# portal.net
KiCad netlist of a schematic drawn in EAGLE
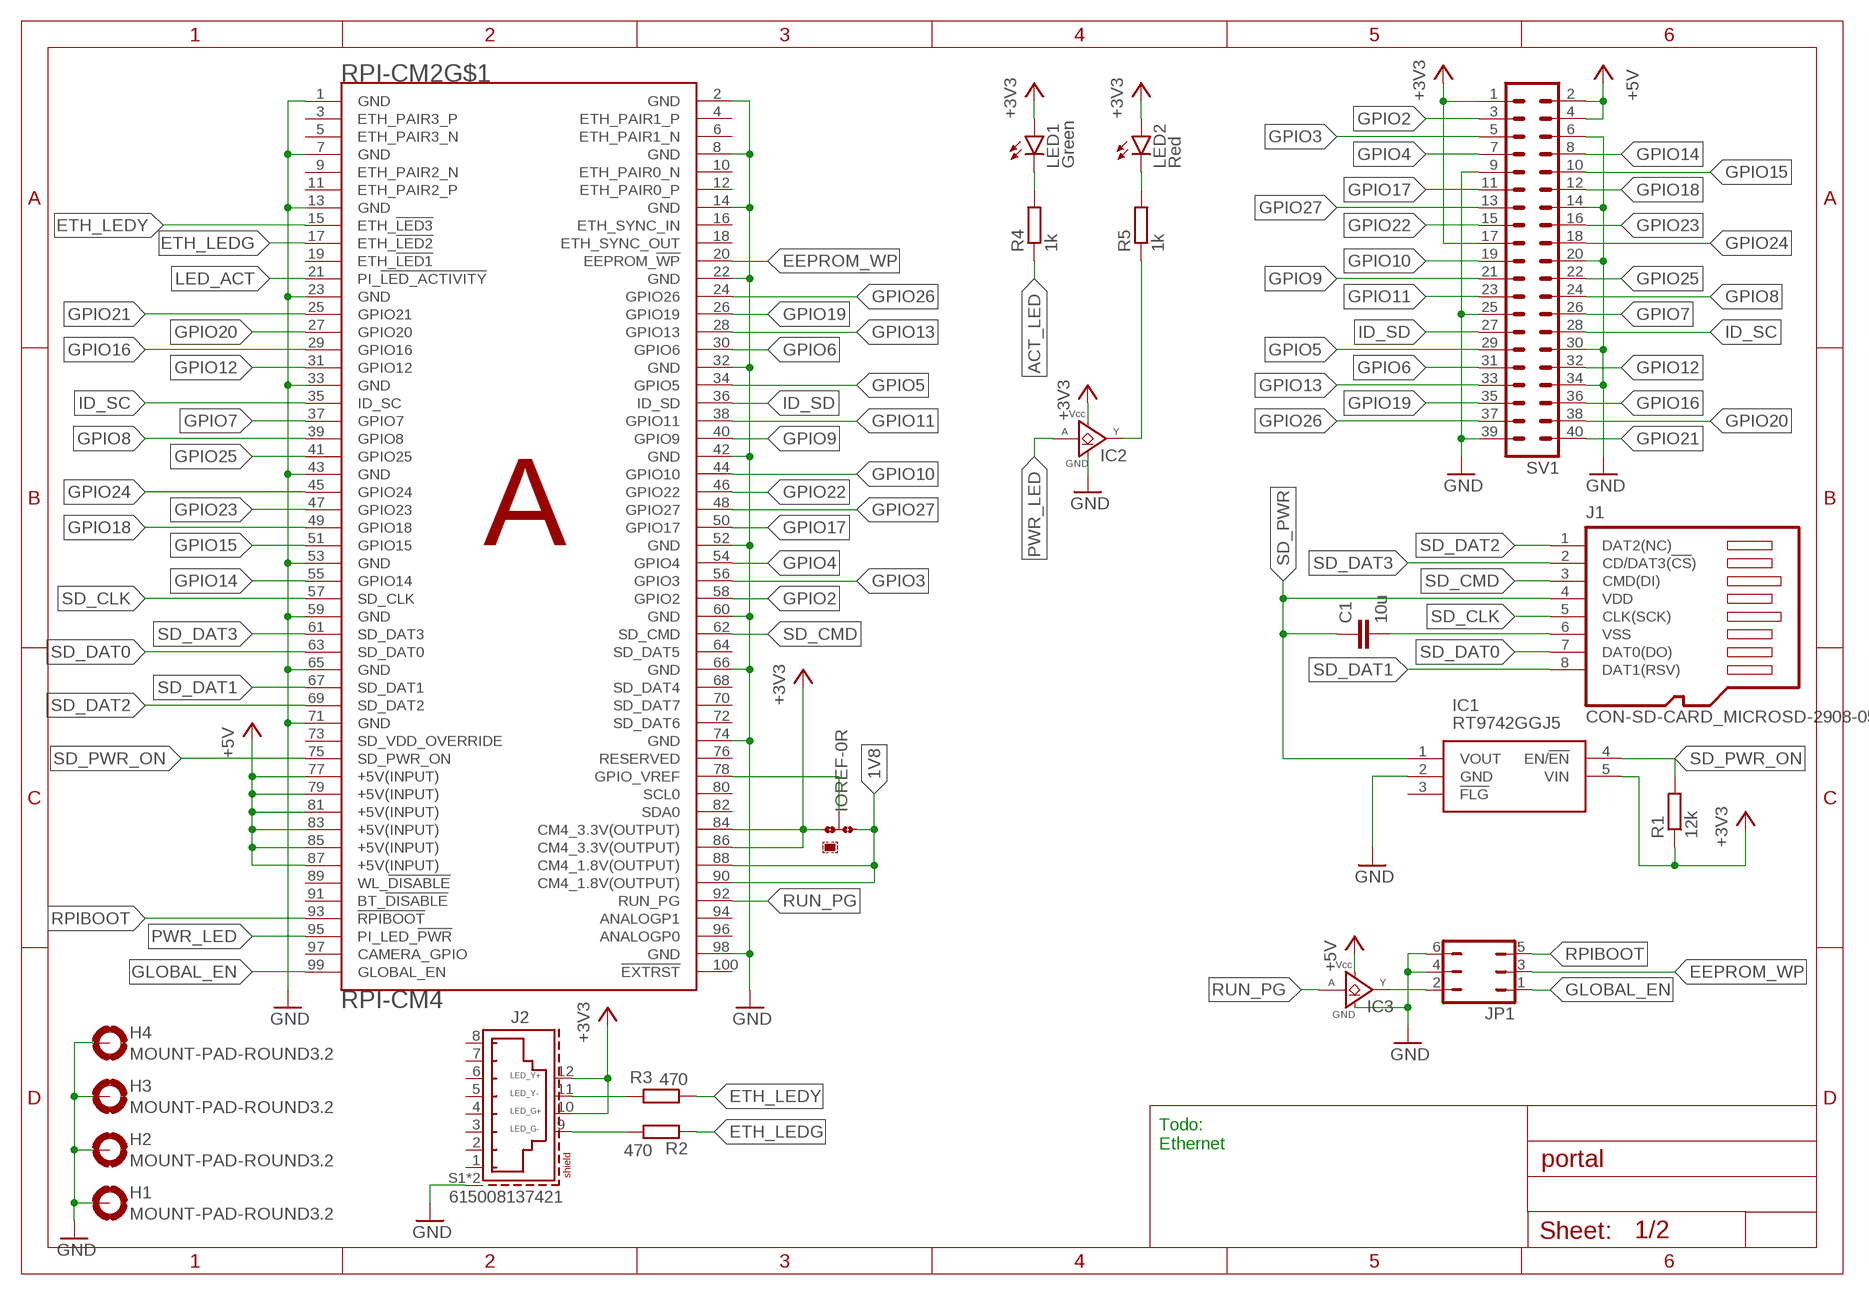
[diagram p0: schematic, sheet 1]
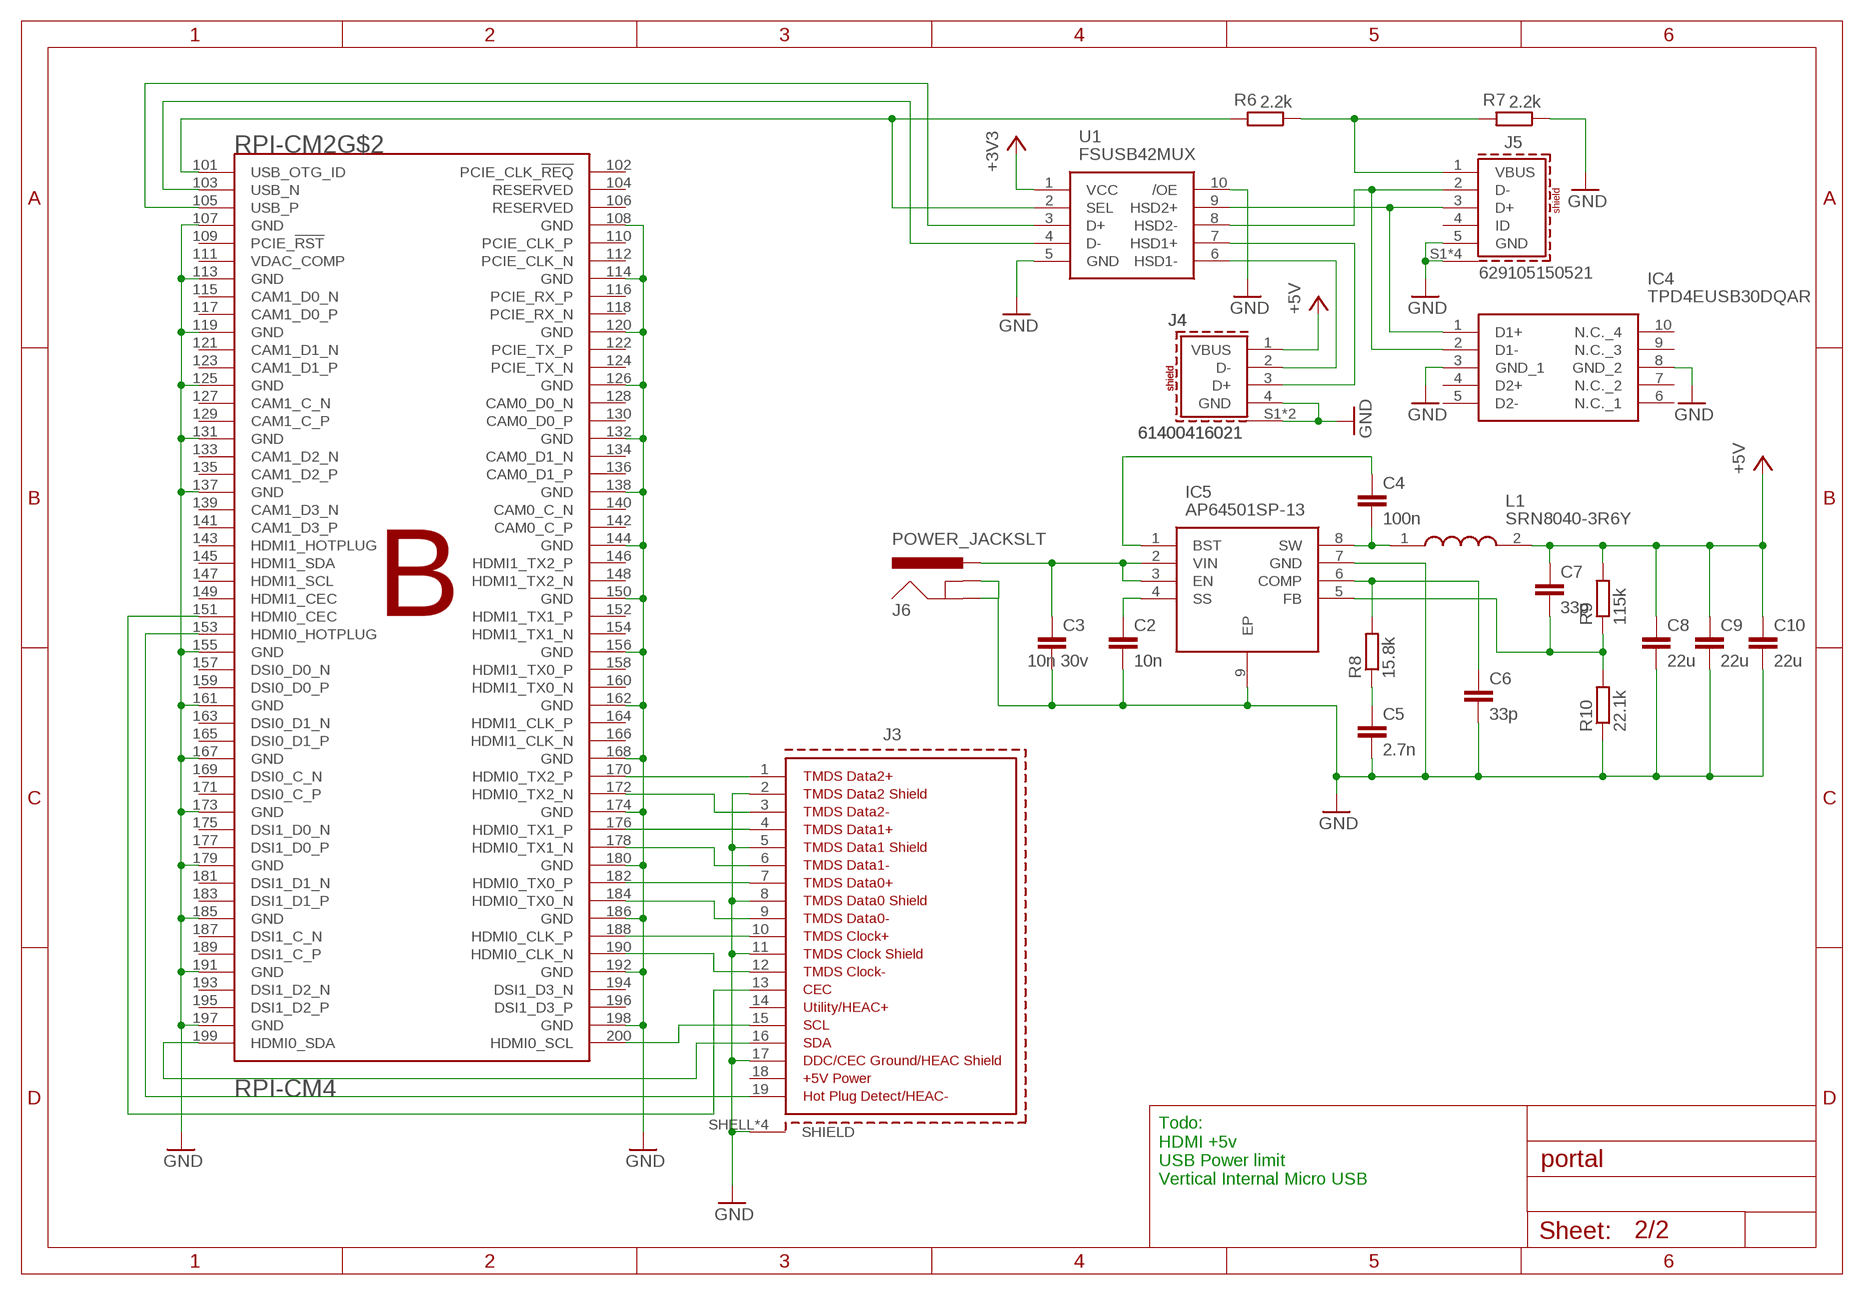
[diagram p1: schematic, sheet 2]

(export (version "E")
  (design (tool "Eeschema 10.0.6"))
  (components
    (comp (ref "C1")
      (value "10u")
      (footprint "eagle-import:C0805")
      (libsource (lib "eagle-import") (part "C-EUC0805"))
    )
    (comp (ref "H1")
      (value "MOUNT-PAD-ROUND3.2")
      (footprint "eagle-import:3,2-PAD")
      (libsource (lib "eagle-import") (part "MOUNT-PAD-ROUND3.2"))
    )
    (comp (ref "H2")
      (value "MOUNT-PAD-ROUND3.2")
      (footprint "eagle-import:3,2-PAD")
      (libsource (lib "eagle-import") (part "MOUNT-PAD-ROUND3.2"))
    )
    (comp (ref "H3")
      (value "MOUNT-PAD-ROUND3.2")
      (footprint "eagle-import:3,2-PAD")
      (libsource (lib "eagle-import") (part "MOUNT-PAD-ROUND3.2"))
    )
    (comp (ref "H4")
      (value "MOUNT-PAD-ROUND3.2")
      (footprint "eagle-import:3,2-PAD")
      (libsource (lib "eagle-import") (part "MOUNT-PAD-ROUND3.2"))
    )
    (comp (ref "IC1")
      (value "RT9742GGJ5")
      (footprint "eagle-import:SOT94P280X100-5N")
      (libsource (lib "eagle-import") (part "RT9742GGJ5"))
    )
    (comp (ref "IC2")
      (value "GHI-IC_SN74LVC1G07DCK")
      (footprint "eagle-import:GHI-IC_SC70(TI-DCK)")
      (libsource (lib "eagle-import") (part "GHI-IC_SN74LVC1G07DCK"))
    )
    (comp (ref "IC3")
      (value "GHI-IC_SN74LVC1G07DCK")
      (footprint "eagle-import:GHI-IC_SC70(TI-DCK)")
      (libsource (lib "eagle-import") (part "GHI-IC_SN74LVC1G07DCK"))
    )
    (comp (ref "IOREF")
      (value "0R-JUMPA")
      (footprint "eagle-import:A0R-JMP")
      (libsource (lib "eagle-import") (part "0R-JUMPA"))
    )
    (comp (ref "J1")
      (value "CON-SD-CARD_MICROSD-2908-05")
      (footprint "eagle-import:CON-SD-CARD_2908-05")
      (libsource (lib "eagle-import") (part "CON-SD-CARD_MICROSD-2908-05"))
    )
    (comp (ref "J2")
      (value "615008137421")
      (footprint "eagle-import:615008137421")
      (libsource (lib "eagle-import") (part "615008137421"))
    )
    (comp (ref "JP1")
      (value "JP3Q")
      (footprint "eagle-import:JP3Q")
      (libsource (lib "eagle-import") (part "JP3Q"))
    )
    (comp (ref "LED1")
      (value "Green")
      (footprint "eagle-import:CHIP-LED0805")
      (libsource (lib "eagle-import") (part "LEDCHIP-LED0805"))
    )
    (comp (ref "LED2")
      (value "Red")
      (footprint "eagle-import:CHIP-LED0805")
      (libsource (lib "eagle-import") (part "LEDCHIP-LED0805"))
    )
    (comp (ref "R1")
      (value "12k")
      (footprint "eagle-import:R0805")
      (libsource (lib "eagle-import") (part "resistor_348_R-EU_R0805"))
    )
    (comp (ref "R2")
      (value "470")
      (footprint "eagle-import:R0805")
      (libsource (lib "eagle-import") (part "R-EU_R0805"))
    )
    (comp (ref "R3")
      (value "470")
      (footprint "eagle-import:R0805")
      (libsource (lib "eagle-import") (part "R-EU_R0805"))
    )
    (comp (ref "R4")
      (value "1k")
      (footprint "eagle-import:R0805")
      (libsource (lib "eagle-import") (part "R-EU_R0805"))
    )
    (comp (ref "R5")
      (value "1k")
      (footprint "eagle-import:R0805")
      (libsource (lib "eagle-import") (part "R-EU_R0805"))
    )
    (comp (ref "RPI-CM2")
      (value "RPI-CM4")
      (footprint "eagle-import:RPI-CM4")
      (libsource (lib "eagle-import") (part "RPI-CM4"))
    )
    (comp (ref "SV1")
      (value "MA20-2")
      (footprint "eagle-import:MA20-2")
      (libsource (lib "eagle-import") (part "MA20-2"))
    )
    (comp (ref "C2")
      (value "10n")
      (footprint "eagle-import:C0805")
      (libsource (lib "eagle-import") (part "C-EUC0805"))
    )
    (comp (ref "C3")
      (value "10n 30v")
      (footprint "eagle-import:C0805")
      (libsource (lib "eagle-import") (part "C-EUC0805"))
    )
    (comp (ref "C4")
      (value "100n")
      (footprint "eagle-import:C0805")
      (libsource (lib "eagle-import") (part "C-EUC0805"))
    )
    (comp (ref "C5")
      (value "2.7n")
      (footprint "eagle-import:C0805")
      (libsource (lib "eagle-import") (part "C-EUC0805"))
    )
    (comp (ref "C6")
      (value "33p")
      (footprint "eagle-import:C0805")
      (libsource (lib "eagle-import") (part "C-EUC0805"))
    )
    (comp (ref "C7")
      (value "33p")
      (footprint "eagle-import:C0805")
      (libsource (lib "eagle-import") (part "C-EUC0805"))
    )
    (comp (ref "C8")
      (value "22u")
      (footprint "eagle-import:C0805")
      (libsource (lib "eagle-import") (part "C-EUC0805"))
    )
    (comp (ref "C9")
      (value "22u")
      (footprint "eagle-import:C0805")
      (libsource (lib "eagle-import") (part "C-EUC0805"))
    )
    (comp (ref "C10")
      (value "22u")
      (footprint "eagle-import:C0805")
      (libsource (lib "eagle-import") (part "C-EUC0805"))
    )
    (comp (ref "IC4")
      (value "TPD4EUSB30DQAR")
      (footprint "eagle-import:DQA(R-PUSON-N10)")
      (fields (field (name "MOUSER_PART_NUMBER") "595-TPD4EUSB30DQAR"))
      (libsource (lib "eagle-import") (part "TPD4EUSB30DQAR"))
    )
    (comp (ref "IC5")
      (value "AP64501SP-13")
      (footprint "eagle-import:SOIC127P600X163-9N")
      (fields (field (name "MOUSER_PART_NUMBER") "621-AP64501SP-13"))
      (libsource (lib "eagle-import") (part "AP64501SP-13"))
    )
    (comp (ref "J3")
      (value "685119134923")
      (footprint "eagle-import:685119134923")
      (libsource (lib "eagle-import") (part "685119134923"))
    )
    (comp (ref "J4")
      (value "61400416021")
      (footprint "eagle-import:61400416021")
      (libsource (lib "eagle-import") (part "61400416021"))
    )
    (comp (ref "J5")
      (value "629105150521")
      (footprint "eagle-import:629105150521")
      (libsource (lib "eagle-import") (part "629105150521"))
    )
    (comp (ref "J6")
      (value "POWER_JACKSLT")
      (footprint "eagle-import:POWER_JACK_SLOT")
      (libsource (lib "eagle-import") (part "POWER_JACKSLT"))
    )
    (comp (ref "L1")
      (value "SRN8040-3R6Y")
      (footprint "eagle-import:SRN80408R2Y")
      (fields (field (name "MOUSER_PART_NUMBER") "652-SRN8040-3R6Y"))
      (libsource (lib "eagle-import") (part "SRN8040-3R6Y"))
    )
    (comp (ref "R6")
      (value "2.2k")
      (footprint "eagle-import:R0805")
      (libsource (lib "eagle-import") (part "R-EU_R0805"))
    )
    (comp (ref "R7")
      (value "2.2k")
      (footprint "eagle-import:R0805")
      (libsource (lib "eagle-import") (part "R-EU_R0805"))
    )
    (comp (ref "R8")
      (value "15.8k")
      (footprint "eagle-import:R0805")
      (libsource (lib "eagle-import") (part "R-EU_R0805"))
    )
    (comp (ref "R9")
      (value "115k")
      (footprint "eagle-import:R0805")
      (libsource (lib "eagle-import") (part "R-EU_R0805"))
    )
    (comp (ref "R10")
      (value "22.1k")
      (footprint "eagle-import:R0805")
      (libsource (lib "eagle-import") (part "R-EU_R0805"))
    )
    (comp (ref "U1")
      (value "FSUSB42MUX")
      (footprint "eagle-import:SOP50P490X110-10N")
      (fields (field (name "MOUSER_PART_NUMBER") "512-FSUSB42MUX"))
      (libsource (lib "eagle-import") (part "FSUSB42MUX"))
    )
  )
  (nets
    (net (code "1") (name "+3V3") (class "Default")
      (node (ref "IC1") (pin "5") (pinfunction "VIN_5") (pintype "bidirectional"))
      (node (ref "IC2") (pin "5") (pinfunction "VCC_5") (pintype "bidirectional"))
      (node (ref "IOREF") (pin "1") (pinfunction "1_1") (pintype "passive"))
      (node (ref "J2") (pin "10") (pinfunction "G+_10") (pintype "passive"))
      (node (ref "J2") (pin "12") (pinfunction "Y+_12") (pintype "passive"))
      (node (ref "LED1") (pin "A") (pinfunction "A_A") (pintype "passive"))
      (node (ref "LED2") (pin "A") (pinfunction "A_A") (pintype "passive"))
      (node (ref "R1") (pin "1") (pinfunction "1_1") (pintype "passive"))
      (node (ref "RPI-CM2") (pin "84") (pinfunction "CM4_3.3V(OUTPUT)_84") (pintype "passive"))
      (node (ref "RPI-CM2") (pin "86") (pinfunction "CM4_3.3V(OUTPUT)_86") (pintype "passive"))
      (node (ref "SV1") (pin "1") (pinfunction "1_1") (pintype "passive"))
      (node (ref "SV1") (pin "17") (pinfunction "17_17") (pintype "passive"))
      (node (ref "U1") (pin "1") (pinfunction "VCC_1") (pintype "bidirectional"))
    )
    (net (code "2") (name "+5V") (class "Default")
      (node (ref "C10") (pin "1") (pinfunction "1_1") (pintype "passive"))
      (node (ref "C7") (pin "1") (pinfunction "1_1") (pintype "passive"))
      (node (ref "C8") (pin "1") (pinfunction "1_1") (pintype "passive"))
      (node (ref "C9") (pin "1") (pinfunction "1_1") (pintype "passive"))
      (node (ref "IC3") (pin "5") (pinfunction "VCC_5") (pintype "bidirectional"))
      (node (ref "J4") (pin "1") (pinfunction "VBUS_1") (pintype "bidirectional"))
      (node (ref "L1") (pin "2") (pinfunction "2_2") (pintype "bidirectional"))
      (node (ref "R9") (pin "2") (pinfunction "2_2") (pintype "passive"))
      (node (ref "RPI-CM2") (pin "77") (pinfunction "+5V(INPUT)_77") (pintype "passive"))
      (node (ref "RPI-CM2") (pin "79") (pinfunction "+5V(INPUT)_79") (pintype "passive"))
      (node (ref "RPI-CM2") (pin "81") (pinfunction "+5V(INPUT)_81") (pintype "passive"))
      (node (ref "RPI-CM2") (pin "83") (pinfunction "+5V(INPUT)_83") (pintype "passive"))
      (node (ref "RPI-CM2") (pin "85") (pinfunction "+5V(INPUT)_85") (pintype "passive"))
      (node (ref "RPI-CM2") (pin "87") (pinfunction "+5V(INPUT)_87") (pintype "passive"))
      (node (ref "SV1") (pin "2") (pinfunction "2_2") (pintype "passive"))
      (node (ref "SV1") (pin "4") (pinfunction "4_4") (pintype "passive"))
    )
    (net (code "3") (name "+5VPOWER") (class "Default")
      (node (ref "J3") (pin "18") (pinfunction "+5VPOWER_18") (pintype "power_in"))
    )
    (net (code "4") (name "1V8") (class "Default")
      (node (ref "IOREF") (pin "3") (pinfunction "3_3") (pintype "passive"))
      (node (ref "RPI-CM2") (pin "88") (pinfunction "CM4_1.8V(OUTPUT)_88") (pintype "passive"))
      (node (ref "RPI-CM2") (pin "90") (pinfunction "CM4_1.8V(OUTPUT)_90") (pintype "passive"))
    )
    (net (code "5") (name "ACT_LED") (class "Default")
      (node (ref "R4") (pin "1") (pinfunction "1_1") (pintype "passive"))
    )
    (net (code "6") (name "EEPROM_WP") (class "Default")
      (node (ref "JP1") (pin "3") (pinfunction "3_3") (pintype "passive"))
      (node (ref "RPI-CM2") (pin "20") (pinfunction "EEPROM_~{WP}_20") (pintype "passive"))
    )
    (net (code "7") (name "ETH_LEDG") (class "Default")
      (node (ref "R2") (pin "1") (pinfunction "1_1") (pintype "passive"))
      (node (ref "RPI-CM2") (pin "17") (pinfunction "ETH_~{LED2}_17") (pintype "passive"))
    )
    (net (code "8") (name "ETH_LEDY") (class "Default")
      (node (ref "R3") (pin "1") (pinfunction "1_1") (pintype "passive"))
      (node (ref "RPI-CM2") (pin "15") (pinfunction "ETH_~{LED3}_15") (pintype "passive"))
    )
    (net (code "9") (name "GLOBAL_EN") (class "Default")
      (node (ref "JP1") (pin "1") (pinfunction "1_1") (pintype "passive"))
      (node (ref "RPI-CM2") (pin "99") (pinfunction "GLOBAL_EN_99") (pintype "passive"))
    )
    (net (code "10") (name "GND") (class "Default")
      (node (ref "C10") (pin "2") (pinfunction "2_2") (pintype "passive"))
      (node (ref "C2") (pin "2") (pinfunction "2_2") (pintype "passive"))
      (node (ref "C3") (pin "2") (pinfunction "2_2") (pintype "passive"))
      (node (ref "C5") (pin "2") (pinfunction "2_2") (pintype "passive"))
      (node (ref "C6") (pin "2") (pinfunction "2_2") (pintype "passive"))
      (node (ref "C8") (pin "2") (pinfunction "2_2") (pintype "passive"))
      (node (ref "C9") (pin "2") (pinfunction "2_2") (pintype "passive"))
      (node (ref "H1") (pin "B3,2") (pinfunction "MOUNT_B3,2") (pintype "passive"))
      (node (ref "H2") (pin "B3,2") (pinfunction "MOUNT_B3,2") (pintype "passive"))
      (node (ref "H3") (pin "B3,2") (pinfunction "MOUNT_B3,2") (pintype "passive"))
      (node (ref "H4") (pin "B3,2") (pinfunction "MOUNT_B3,2") (pintype "passive"))
      (node (ref "IC1") (pin "2") (pinfunction "GND_2") (pintype "bidirectional"))
      (node (ref "IC2") (pin "3") (pinfunction "GND_3") (pintype "bidirectional"))
      (node (ref "IC3") (pin "3") (pinfunction "GND_3") (pintype "bidirectional"))
      (node (ref "IC4") (pin "3") (pinfunction "GND_1_3") (pintype "bidirectional"))
      (node (ref "IC4") (pin "8") (pinfunction "GND_2_8") (pintype "bidirectional"))
      (node (ref "IC5") (pin "7") (pinfunction "GND_7") (pintype "bidirectional"))
      (node (ref "IC5") (pin "9") (pinfunction "EP_9") (pintype "bidirectional"))
      (node (ref "J2") (pin "S1") (pinfunction "SHIELD_S1") (pintype "passive"))
      (node (ref "J2") (pin "S2") (pinfunction "SHIELD_S2") (pintype "passive"))
      (node (ref "J3") (pin "11") (pinfunction "TMDSCLOCKSHIELD_11") (pintype "passive"))
      (node (ref "J3") (pin "17") (pinfunction "DDC/CEC/HECGROUND_17") (pintype "passive"))
      (node (ref "J3") (pin "2") (pinfunction "TMDSDATA2SHIELD_2") (pintype "passive"))
      (node (ref "J3") (pin "5") (pinfunction "TMDSDATA1SHIELD_5") (pintype "passive"))
      (node (ref "J3") (pin "8") (pinfunction "TMDSDATA0SHIELD_8") (pintype "passive"))
      (node (ref "J3") (pin "SHELL") (pinfunction "SHIELD_SHELL") (pintype "passive"))
      (node (ref "J3") (pin "SHELL1") (pinfunction "SHIELD_SHELL1") (pintype "passive"))
      (node (ref "J3") (pin "SHELL2") (pinfunction "SHIELD_SHELL2") (pintype "passive"))
      (node (ref "J3") (pin "SHELL3") (pinfunction "SHIELD_SHELL3") (pintype "passive"))
      (node (ref "J4") (pin "4") (pinfunction "GND_4") (pintype "bidirectional"))
      (node (ref "J4") (pin "S1") (pinfunction "SHIELD_S1") (pintype "bidirectional"))
      (node (ref "J4") (pin "S2") (pinfunction "SHIELD_S2") (pintype "bidirectional"))
      (node (ref "J5") (pin "5") (pinfunction "GND_5") (pintype "passive"))
      (node (ref "J5") (pin "S1") (pinfunction "SHIELD_S1") (pintype "passive"))
      (node (ref "J5") (pin "S2") (pinfunction "SHIELD_S2") (pintype "passive"))
      (node (ref "J5") (pin "S3") (pinfunction "SHIELD_S3") (pintype "passive"))
      (node (ref "J5") (pin "S4") (pinfunction "SHIELD_S4") (pintype "passive"))
      (node (ref "J6") (pin "GND@1") (pinfunction "GNDBREAK_GND@1") (pintype "bidirectional"))
      (node (ref "J6") (pin "GND@2") (pinfunction "GND_GND@2") (pintype "bidirectional"))
      (node (ref "JP1") (pin "4") (pinfunction "4_4") (pintype "passive"))
      (node (ref "JP1") (pin "6") (pinfunction "6_6") (pintype "passive"))
      (node (ref "R10") (pin "1") (pinfunction "1_1") (pintype "passive"))
      (node (ref "R7") (pin "1") (pinfunction "1_1") (pintype "passive"))
      (node (ref "RPI-CM2") (pin "1") (pinfunction "GND_1") (pintype "passive"))
      (node (ref "RPI-CM2") (pin "107") (pinfunction "GND_107") (pintype "passive"))
      (node (ref "RPI-CM2") (pin "108") (pinfunction "GND_108") (pintype "passive"))
      (node (ref "RPI-CM2") (pin "113") (pinfunction "GND_113") (pintype "passive"))
      (node (ref "RPI-CM2") (pin "114") (pinfunction "GND_114") (pintype "passive"))
      (node (ref "RPI-CM2") (pin "119") (pinfunction "GND_119") (pintype "passive"))
      (node (ref "RPI-CM2") (pin "120") (pinfunction "GND_120") (pintype "passive"))
      (node (ref "RPI-CM2") (pin "125") (pinfunction "GND_125") (pintype "passive"))
      (node (ref "RPI-CM2") (pin "126") (pinfunction "GND_126") (pintype "passive"))
      (node (ref "RPI-CM2") (pin "13") (pinfunction "GND_13") (pintype "passive"))
      (node (ref "RPI-CM2") (pin "131") (pinfunction "GND_131") (pintype "passive"))
      (node (ref "RPI-CM2") (pin "132") (pinfunction "GND_132") (pintype "passive"))
      (node (ref "RPI-CM2") (pin "137") (pinfunction "GND_137") (pintype "passive"))
      (node (ref "RPI-CM2") (pin "138") (pinfunction "GND_138") (pintype "passive"))
      (node (ref "RPI-CM2") (pin "14") (pinfunction "GND_14") (pintype "passive"))
      (node (ref "RPI-CM2") (pin "144") (pinfunction "GND_144") (pintype "passive"))
      (node (ref "RPI-CM2") (pin "150") (pinfunction "GND_150") (pintype "passive"))
      (node (ref "RPI-CM2") (pin "155") (pinfunction "GND_155") (pintype "passive"))
      (node (ref "RPI-CM2") (pin "156") (pinfunction "GND_156") (pintype "passive"))
      (node (ref "RPI-CM2") (pin "161") (pinfunction "GND_161") (pintype "passive"))
      (node (ref "RPI-CM2") (pin "162") (pinfunction "GND_162") (pintype "passive"))
      (node (ref "RPI-CM2") (pin "167") (pinfunction "GND_167") (pintype "passive"))
      (node (ref "RPI-CM2") (pin "168") (pinfunction "GND_168") (pintype "passive"))
      (node (ref "RPI-CM2") (pin "173") (pinfunction "GND_173") (pintype "passive"))
      (node (ref "RPI-CM2") (pin "174") (pinfunction "GND_174") (pintype "passive"))
      (node (ref "RPI-CM2") (pin "179") (pinfunction "GND_179") (pintype "passive"))
      (node (ref "RPI-CM2") (pin "180") (pinfunction "GND_180") (pintype "passive"))
      (node (ref "RPI-CM2") (pin "185") (pinfunction "GND_185") (pintype "passive"))
      (node (ref "RPI-CM2") (pin "186") (pinfunction "GND_186") (pintype "passive"))
      (node (ref "RPI-CM2") (pin "191") (pinfunction "GND_191") (pintype "passive"))
      (node (ref "RPI-CM2") (pin "192") (pinfunction "GND_192") (pintype "passive"))
      (node (ref "RPI-CM2") (pin "197") (pinfunction "GND_197") (pintype "passive"))
      (node (ref "RPI-CM2") (pin "198") (pinfunction "GND_198") (pintype "passive"))
      (node (ref "RPI-CM2") (pin "2") (pinfunction "GND_2") (pintype "passive"))
      (node (ref "RPI-CM2") (pin "22") (pinfunction "GND_22") (pintype "passive"))
      (node (ref "RPI-CM2") (pin "23") (pinfunction "GND_23") (pintype "passive"))
      (node (ref "RPI-CM2") (pin "32") (pinfunction "GND_32") (pintype "passive"))
      (node (ref "RPI-CM2") (pin "33") (pinfunction "GND_33") (pintype "passive"))
      (node (ref "RPI-CM2") (pin "42") (pinfunction "GND_42") (pintype "passive"))
      (node (ref "RPI-CM2") (pin "43") (pinfunction "GND_43") (pintype "passive"))
      (node (ref "RPI-CM2") (pin "52") (pinfunction "GND_52") (pintype "passive"))
      (node (ref "RPI-CM2") (pin "53") (pinfunction "GND_53") (pintype "passive"))
      (node (ref "RPI-CM2") (pin "59") (pinfunction "GND_59") (pintype "passive"))
      (node (ref "RPI-CM2") (pin "60") (pinfunction "GND_60") (pintype "passive"))
      (node (ref "RPI-CM2") (pin "65") (pinfunction "GND_65") (pintype "passive"))
      (node (ref "RPI-CM2") (pin "66") (pinfunction "GND_66") (pintype "passive"))
      (node (ref "RPI-CM2") (pin "7") (pinfunction "GND_7") (pintype "passive"))
      (node (ref "RPI-CM2") (pin "71") (pinfunction "GND_71") (pintype "passive"))
      (node (ref "RPI-CM2") (pin "74") (pinfunction "GND_74") (pintype "passive"))
      (node (ref "RPI-CM2") (pin "8") (pinfunction "GND_8") (pintype "passive"))
      (node (ref "RPI-CM2") (pin "98") (pinfunction "GND_98") (pintype "passive"))
      (node (ref "SV1") (pin "14") (pinfunction "14_14") (pintype "passive"))
      (node (ref "SV1") (pin "20") (pinfunction "20_20") (pintype "passive"))
      (node (ref "SV1") (pin "25") (pinfunction "25_25") (pintype "passive"))
      (node (ref "SV1") (pin "30") (pinfunction "30_30") (pintype "passive"))
      (node (ref "SV1") (pin "34") (pinfunction "34_34") (pintype "passive"))
      (node (ref "SV1") (pin "39") (pinfunction "39_39") (pintype "passive"))
      (node (ref "SV1") (pin "6") (pinfunction "6_6") (pintype "passive"))
      (node (ref "SV1") (pin "9") (pinfunction "9_9") (pintype "passive"))
      (node (ref "U1") (pin "10") (pinfunction "/OE_10") (pintype "bidirectional"))
      (node (ref "U1") (pin "5") (pinfunction "GND_5") (pintype "bidirectional"))
    )
    (net (code "11") (name "GPIO2") (class "Default")
      (node (ref "RPI-CM2") (pin "58") (pinfunction "GPIO2_58") (pintype "passive"))
      (node (ref "SV1") (pin "3") (pinfunction "3_3") (pintype "passive"))
    )
    (net (code "12") (name "GPIO3") (class "Default")
      (node (ref "RPI-CM2") (pin "56") (pinfunction "GPIO3_56") (pintype "passive"))
      (node (ref "SV1") (pin "5") (pinfunction "5_5") (pintype "passive"))
    )
    (net (code "13") (name "GPIO4") (class "Default")
      (node (ref "RPI-CM2") (pin "54") (pinfunction "GPIO4_54") (pintype "passive"))
      (node (ref "SV1") (pin "7") (pinfunction "7_7") (pintype "passive"))
    )
    (net (code "14") (name "GPIO5") (class "Default")
      (node (ref "RPI-CM2") (pin "34") (pinfunction "GPIO5_34") (pintype "passive"))
      (node (ref "SV1") (pin "29") (pinfunction "29_29") (pintype "passive"))
    )
    (net (code "15") (name "GPIO6") (class "Default")
      (node (ref "RPI-CM2") (pin "30") (pinfunction "GPIO6_30") (pintype "passive"))
      (node (ref "SV1") (pin "31") (pinfunction "31_31") (pintype "passive"))
    )
    (net (code "16") (name "GPIO7") (class "Default")
      (node (ref "RPI-CM2") (pin "37") (pinfunction "GPIO7_37") (pintype "passive"))
      (node (ref "SV1") (pin "26") (pinfunction "26_26") (pintype "passive"))
    )
    (net (code "17") (name "GPIO8") (class "Default")
      (node (ref "RPI-CM2") (pin "39") (pinfunction "GPIO8_39") (pintype "passive"))
      (node (ref "SV1") (pin "24") (pinfunction "24_24") (pintype "passive"))
    )
    (net (code "18") (name "GPIO9") (class "Default")
      (node (ref "RPI-CM2") (pin "40") (pinfunction "GPIO9_40") (pintype "passive"))
      (node (ref "SV1") (pin "21") (pinfunction "21_21") (pintype "passive"))
    )
    (net (code "19") (name "GPIO10") (class "Default")
      (node (ref "RPI-CM2") (pin "44") (pinfunction "GPIO10_44") (pintype "passive"))
      (node (ref "SV1") (pin "19") (pinfunction "19_19") (pintype "passive"))
    )
    (net (code "20") (name "GPIO11") (class "Default")
      (node (ref "RPI-CM2") (pin "38") (pinfunction "GPIO11_38") (pintype "passive"))
      (node (ref "SV1") (pin "23") (pinfunction "23_23") (pintype "passive"))
    )
    (net (code "21") (name "GPIO12") (class "Default")
      (node (ref "RPI-CM2") (pin "31") (pinfunction "GPIO12_31") (pintype "passive"))
      (node (ref "SV1") (pin "32") (pinfunction "32_32") (pintype "passive"))
    )
    (net (code "22") (name "GPIO13") (class "Default")
      (node (ref "RPI-CM2") (pin "28") (pinfunction "GPIO13_28") (pintype "passive"))
      (node (ref "SV1") (pin "33") (pinfunction "33_33") (pintype "passive"))
    )
    (net (code "23") (name "GPIO14") (class "Default")
      (node (ref "RPI-CM2") (pin "55") (pinfunction "GPIO14_55") (pintype "passive"))
      (node (ref "SV1") (pin "8") (pinfunction "8_8") (pintype "passive"))
    )
    (net (code "24") (name "GPIO15") (class "Default")
      (node (ref "RPI-CM2") (pin "51") (pinfunction "GPIO15_51") (pintype "passive"))
      (node (ref "SV1") (pin "10") (pinfunction "10_10") (pintype "passive"))
    )
    (net (code "25") (name "GPIO16") (class "Default")
      (node (ref "RPI-CM2") (pin "29") (pinfunction "GPIO16_29") (pintype "passive"))
      (node (ref "SV1") (pin "36") (pinfunction "36_36") (pintype "passive"))
    )
    (net (code "26") (name "GPIO17") (class "Default")
      (node (ref "RPI-CM2") (pin "50") (pinfunction "GPIO17_50") (pintype "passive"))
      (node (ref "SV1") (pin "11") (pinfunction "11_11") (pintype "passive"))
    )
    (net (code "27") (name "GPIO18") (class "Default")
      (node (ref "RPI-CM2") (pin "49") (pinfunction "GPIO18_49") (pintype "passive"))
      (node (ref "SV1") (pin "12") (pinfunction "12_12") (pintype "passive"))
    )
    (net (code "28") (name "GPIO19") (class "Default")
      (node (ref "RPI-CM2") (pin "26") (pinfunction "GPIO19_26") (pintype "passive"))
      (node (ref "SV1") (pin "35") (pinfunction "35_35") (pintype "passive"))
    )
    (net (code "29") (name "GPIO20") (class "Default")
      (node (ref "RPI-CM2") (pin "27") (pinfunction "GPIO20_27") (pintype "passive"))
      (node (ref "SV1") (pin "38") (pinfunction "38_38") (pintype "passive"))
    )
    (net (code "30") (name "GPIO21") (class "Default")
      (node (ref "RPI-CM2") (pin "25") (pinfunction "GPIO21_25") (pintype "passive"))
      (node (ref "SV1") (pin "40") (pinfunction "40_40") (pintype "passive"))
    )
    (net (code "31") (name "GPIO22") (class "Default")
      (node (ref "RPI-CM2") (pin "46") (pinfunction "GPIO22_46") (pintype "passive"))
      (node (ref "SV1") (pin "15") (pinfunction "15_15") (pintype "passive"))
    )
    (net (code "32") (name "GPIO23") (class "Default")
      (node (ref "RPI-CM2") (pin "47") (pinfunction "GPIO23_47") (pintype "passive"))
      (node (ref "SV1") (pin "16") (pinfunction "16_16") (pintype "passive"))
    )
    (net (code "33") (name "GPIO24") (class "Default")
      (node (ref "RPI-CM2") (pin "45") (pinfunction "GPIO24_45") (pintype "passive"))
      (node (ref "SV1") (pin "18") (pinfunction "18_18") (pintype "passive"))
    )
    (net (code "34") (name "GPIO25") (class "Default")
      (node (ref "RPI-CM2") (pin "41") (pinfunction "GPIO25_41") (pintype "passive"))
      (node (ref "SV1") (pin "22") (pinfunction "22_22") (pintype "passive"))
    )
    (net (code "35") (name "GPIO26") (class "Default")
      (node (ref "RPI-CM2") (pin "24") (pinfunction "GPIO26_24") (pintype "passive"))
      (node (ref "SV1") (pin "37") (pinfunction "37_37") (pintype "passive"))
    )
    (net (code "36") (name "GPIO27") (class "Default")
      (node (ref "RPI-CM2") (pin "48") (pinfunction "GPIO27_48") (pintype "passive"))
      (node (ref "SV1") (pin "13") (pinfunction "13_13") (pintype "passive"))
    )
    (net (code "37") (name "ID_SC") (class "Default")
      (node (ref "RPI-CM2") (pin "35") (pinfunction "ID_SC_35") (pintype "passive"))
      (node (ref "SV1") (pin "28") (pinfunction "28_28") (pintype "passive"))
    )
    (net (code "38") (name "ID_SD") (class "Default")
      (node (ref "RPI-CM2") (pin "36") (pinfunction "ID_SD_36") (pintype "passive"))
      (node (ref "SV1") (pin "27") (pinfunction "27_27") (pintype "passive"))
    )
    (net (code "39") (name "LED_ACT") (class "Default")
      (node (ref "RPI-CM2") (pin "21") (pinfunction "PI_~{LED_ACTIVITY}_21") (pintype "passive"))
    )
    (net (code "40") (name "Net-(C5-Pad1)") (class "Default")
      (node (ref "C5") (pin "1") (pinfunction "1_1") (pintype "passive"))
      (node (ref "R8") (pin "1") (pinfunction "1_1") (pintype "passive"))
    )
    (net (code "41") (name "Net-(IC2-Y)") (class "Default")
      (node (ref "IC2") (pin "4") (pinfunction "Y_4") (pintype "bidirectional"))
      (node (ref "R5") (pin "1") (pinfunction "1_1") (pintype "passive"))
    )
    (net (code "42") (name "Net-(IC3-Y)") (class "Default")
      (node (ref "IC3") (pin "4") (pinfunction "Y_4") (pintype "bidirectional"))
      (node (ref "JP1") (pin "2") (pinfunction "2_2") (pintype "passive"))
    )
    (net (code "43") (name "Net-(IC4-D1+)") (class "Default")
      (node (ref "IC4") (pin "1") (pinfunction "D1+_1") (pintype "bidirectional"))
      (node (ref "J5") (pin "3") (pinfunction "D+_3") (pintype "passive"))
      (node (ref "U1") (pin "9") (pinfunction "HSD2+_9") (pintype "bidirectional"))
    )
    (net (code "44") (name "Net-(IC4-D1-)") (class "Default")
      (node (ref "IC4") (pin "2") (pinfunction "D1-_2") (pintype "bidirectional"))
      (node (ref "J5") (pin "2") (pinfunction "D-_2") (pintype "passive"))
      (node (ref "U1") (pin "8") (pinfunction "HSD2-_8") (pintype "bidirectional"))
    )
    (net (code "45") (name "Net-(IC5-BST)") (class "Default")
      (node (ref "C4") (pin "1") (pinfunction "1_1") (pintype "passive"))
      (node (ref "IC5") (pin "1") (pinfunction "BST_1") (pintype "bidirectional"))
    )
    (net (code "46") (name "Net-(IC5-COMP)") (class "Default")
      (node (ref "C6") (pin "1") (pinfunction "1_1") (pintype "passive"))
      (node (ref "IC5") (pin "6") (pinfunction "COMP_6") (pintype "bidirectional"))
      (node (ref "R8") (pin "2") (pinfunction "2_2") (pintype "passive"))
    )
    (net (code "47") (name "Net-(IC5-EN)") (class "Default")
      (node (ref "C3") (pin "1") (pinfunction "1_1") (pintype "passive"))
      (node (ref "IC5") (pin "2") (pinfunction "VIN_2") (pintype "bidirectional"))
      (node (ref "IC5") (pin "3") (pinfunction "EN_3") (pintype "bidirectional"))
      (node (ref "J6") (pin "PWR") (pinfunction "PWR_PWR") (pintype "bidirectional"))
    )
    (net (code "48") (name "Net-(IC5-FB)") (class "Default")
      (node (ref "C7") (pin "2") (pinfunction "2_2") (pintype "passive"))
      (node (ref "IC5") (pin "5") (pinfunction "FB_5") (pintype "bidirectional"))
      (node (ref "R10") (pin "2") (pinfunction "2_2") (pintype "passive"))
      (node (ref "R9") (pin "1") (pinfunction "1_1") (pintype "passive"))
    )
    (net (code "49") (name "Net-(IC5-SS)") (class "Default")
      (node (ref "C2") (pin "1") (pinfunction "1_1") (pintype "passive"))
      (node (ref "IC5") (pin "4") (pinfunction "SS_4") (pintype "bidirectional"))
    )
    (net (code "50") (name "Net-(IC5-SW)") (class "Default")
      (node (ref "C4") (pin "2") (pinfunction "2_2") (pintype "passive"))
      (node (ref "IC5") (pin "8") (pinfunction "SW_8") (pintype "bidirectional"))
      (node (ref "L1") (pin "1") (pinfunction "1_1") (pintype "bidirectional"))
    )
    (net (code "51") (name "Net-(J1B-VSS)") (class "Default")
      (node (ref "C1") (pin "2") (pinfunction "2_2") (pintype "passive"))
      (node (ref "J1") (pin "6") (pinfunction "VSS_6") (pintype "bidirectional"))
    )
    (net (code "52") (name "Net-(J2-G-)") (class "Default")
      (node (ref "J2") (pin "9") (pinfunction "G-_9") (pintype "passive"))
      (node (ref "R2") (pin "2") (pinfunction "2_2") (pintype "passive"))
    )
    (net (code "53") (name "Net-(J2-Y-)") (class "Default")
      (node (ref "J2") (pin "11") (pinfunction "Y-_11") (pintype "passive"))
      (node (ref "R3") (pin "2") (pinfunction "2_2") (pintype "passive"))
    )
    (net (code "54") (name "Net-(J3-CEC)") (class "Default")
      (node (ref "J3") (pin "13") (pinfunction "CEC_13") (pintype "passive"))
      (node (ref "RPI-CM2") (pin "151") (pinfunction "HDMI0_CEC_151") (pintype "passive"))
    )
    (net (code "55") (name "Net-(J3-HOTPLUGDETECT{slash}HEAC-)") (class "Default")
      (node (ref "J3") (pin "19") (pinfunction "HOTPLUGDETECT/HEAC-_19") (pintype "passive"))
      (node (ref "RPI-CM2") (pin "153") (pinfunction "HDMI0_HOTPLUG_153") (pintype "passive"))
    )
    (net (code "56") (name "Net-(J3-SCL)") (class "Default")
      (node (ref "J3") (pin "15") (pinfunction "SCL_15") (pintype "passive"))
      (node (ref "RPI-CM2") (pin "200") (pinfunction "HDMI0_SCL_200") (pintype "passive"))
    )
    (net (code "57") (name "Net-(J3-SDA)") (class "Default")
      (node (ref "J3") (pin "16") (pinfunction "SDA_16") (pintype "passive"))
      (node (ref "RPI-CM2") (pin "199") (pinfunction "HDMI0_SDA_199") (pintype "passive"))
    )
    (net (code "58") (name "Net-(J3-TMDSCLOCK+)") (class "Default")
      (node (ref "J3") (pin "10") (pinfunction "TMDSCLOCK+_10") (pintype "passive"))
      (node (ref "RPI-CM2") (pin "188") (pinfunction "HDMI0_CLK_P_188") (pintype "passive"))
    )
    (net (code "59") (name "Net-(J3-TMDSCLOCK-)") (class "Default")
      (node (ref "J3") (pin "12") (pinfunction "TMDSCLOCK-_12") (pintype "passive"))
      (node (ref "RPI-CM2") (pin "190") (pinfunction "HDMI0_CLK_N_190") (pintype "passive"))
    )
    (net (code "60") (name "Net-(J3-TMDSDATA0+)") (class "Default")
      (node (ref "J3") (pin "7") (pinfunction "TMDSDATA0+_7") (pintype "passive"))
      (node (ref "RPI-CM2") (pin "182") (pinfunction "HDMI0_TX0_P_182") (pintype "passive"))
    )
    (net (code "61") (name "Net-(J3-TMDSDATA0-)") (class "Default")
      (node (ref "J3") (pin "9") (pinfunction "TMDSDATA0-_9") (pintype "passive"))
      (node (ref "RPI-CM2") (pin "184") (pinfunction "HDMI0_TX0_N_184") (pintype "passive"))
    )
    (net (code "62") (name "Net-(J3-TMDSDATA1+)") (class "Default")
      (node (ref "J3") (pin "4") (pinfunction "TMDSDATA1+_4") (pintype "passive"))
      (node (ref "RPI-CM2") (pin "176") (pinfunction "HDMI0_TX1_P_176") (pintype "passive"))
    )
    (net (code "63") (name "Net-(J3-TMDSDATA1-)") (class "Default")
      (node (ref "J3") (pin "6") (pinfunction "TMDSDATA1-_6") (pintype "passive"))
      (node (ref "RPI-CM2") (pin "178") (pinfunction "HDMI0_TX1_N_178") (pintype "passive"))
    )
    (net (code "64") (name "Net-(J3-TMDSDATA2+)") (class "Default")
      (node (ref "J3") (pin "1") (pinfunction "TMDSDATA2+_1") (pintype "passive"))
      (node (ref "RPI-CM2") (pin "170") (pinfunction "HDMI0_TX2_P_170") (pintype "passive"))
    )
    (net (code "65") (name "Net-(J3-TMDSDATA2-)") (class "Default")
      (node (ref "J3") (pin "3") (pinfunction "TMDSDATA2-_3") (pintype "passive"))
      (node (ref "RPI-CM2") (pin "172") (pinfunction "HDMI0_TX2_N_172") (pintype "passive"))
    )
    (net (code "66") (name "Net-(J4-D+)") (class "Default")
      (node (ref "J4") (pin "3") (pinfunction "D+_3") (pintype "bidirectional"))
      (node (ref "U1") (pin "7") (pinfunction "HSD1+_7") (pintype "power_in"))
    )
    (net (code "67") (name "Net-(J4-D-)") (class "Default")
      (node (ref "J4") (pin "2") (pinfunction "D-_2") (pintype "bidirectional"))
      (node (ref "U1") (pin "6") (pinfunction "HSD1-_6") (pintype "bidirectional"))
    )
    (net (code "68") (name "Net-(J5-VBUS)") (class "Default")
      (node (ref "J5") (pin "1") (pinfunction "VBUS_1") (pintype "passive"))
      (node (ref "R6") (pin "1") (pinfunction "1_1") (pintype "passive"))
      (node (ref "R7") (pin "2") (pinfunction "2_2") (pintype "passive"))
    )
    (net (code "69") (name "Net-(LED1-PadC)") (class "Default")
      (node (ref "LED1") (pin "C") (pinfunction "C_C") (pintype "passive"))
      (node (ref "R4") (pin "2") (pinfunction "2_2") (pintype "passive"))
    )
    (net (code "70") (name "Net-(LED2-PadC)") (class "Default")
      (node (ref "LED2") (pin "C") (pinfunction "C_C") (pintype "passive"))
      (node (ref "R5") (pin "2") (pinfunction "2_2") (pintype "passive"))
    )
    (net (code "71") (name "Net-(RPI-CM2A-GPIO_VREF)") (class "Default")
      (node (ref "IOREF") (pin "2") (pinfunction "2_2") (pintype "passive"))
      (node (ref "RPI-CM2") (pin "78") (pinfunction "GPIO_VREF_78") (pintype "passive"))
    )
    (net (code "72") (name "Net-(RPI-CM2B-USB_N)") (class "Default")
      (node (ref "RPI-CM2") (pin "103") (pinfunction "USB_N_103") (pintype "passive"))
      (node (ref "U1") (pin "4") (pinfunction "D-_4") (pintype "bidirectional"))
    )
    (net (code "73") (name "Net-(RPI-CM2B-USB_OTG_ID)") (class "Default")
      (node (ref "R6") (pin "2") (pinfunction "2_2") (pintype "passive"))
      (node (ref "RPI-CM2") (pin "101") (pinfunction "USB_OTG_ID_101") (pintype "passive"))
      (node (ref "U1") (pin "2") (pinfunction "SEL_2") (pintype "bidirectional"))
    )
    (net (code "74") (name "Net-(RPI-CM2B-USB_P)") (class "Default")
      (node (ref "RPI-CM2") (pin "105") (pinfunction "USB_P_105") (pintype "passive"))
      (node (ref "U1") (pin "3") (pinfunction "D+_3") (pintype "bidirectional"))
    )
    (net (code "75") (name "PWR_LED") (class "Default")
      (node (ref "IC2") (pin "2") (pinfunction "A_2") (pintype "bidirectional"))
      (node (ref "RPI-CM2") (pin "95") (pinfunction "PI_LED_~{PWR}_95") (pintype "passive"))
    )
    (net (code "76") (name "RPIBOOT") (class "Default")
      (node (ref "JP1") (pin "5") (pinfunction "5_5") (pintype "passive"))
      (node (ref "RPI-CM2") (pin "93") (pinfunction "~{RPIBOOT}_93") (pintype "passive"))
    )
    (net (code "77") (name "RUN_PG") (class "Default")
      (node (ref "IC3") (pin "2") (pinfunction "A_2") (pintype "bidirectional"))
      (node (ref "RPI-CM2") (pin "92") (pinfunction "RUN_PG_92") (pintype "passive"))
    )
    (net (code "78") (name "SD_CLK") (class "Default")
      (node (ref "J1") (pin "5") (pinfunction "CLK(SCK)_5") (pintype "bidirectional"))
      (node (ref "RPI-CM2") (pin "57") (pinfunction "SD_CLK_57") (pintype "passive"))
    )
    (net (code "79") (name "SD_CMD") (class "Default")
      (node (ref "J1") (pin "3") (pinfunction "CMD(DI)_3") (pintype "bidirectional"))
      (node (ref "RPI-CM2") (pin "62") (pinfunction "SD_CMD_62") (pintype "passive"))
    )
    (net (code "80") (name "SD_DAT0") (class "Default")
      (node (ref "J1") (pin "7") (pinfunction "DAT0(DO)_7") (pintype "bidirectional"))
      (node (ref "RPI-CM2") (pin "63") (pinfunction "SD_DAT0_63") (pintype "passive"))
    )
    (net (code "81") (name "SD_DAT1") (class "Default")
      (node (ref "J1") (pin "8") (pinfunction "DAT1(RSV)_8") (pintype "bidirectional"))
      (node (ref "RPI-CM2") (pin "67") (pinfunction "SD_DAT1_67") (pintype "passive"))
    )
    (net (code "82") (name "SD_DAT2") (class "Default")
      (node (ref "J1") (pin "1") (pinfunction "DAT2(NC)_1") (pintype "bidirectional"))
      (node (ref "RPI-CM2") (pin "69") (pinfunction "SD_DAT2_69") (pintype "passive"))
    )
    (net (code "83") (name "SD_DAT3") (class "Default")
      (node (ref "J1") (pin "2") (pinfunction "CD/DAT3(~{CS})_2") (pintype "bidirectional"))
      (node (ref "RPI-CM2") (pin "61") (pinfunction "SD_DAT3_61") (pintype "passive"))
    )
    (net (code "84") (name "SD_PWR") (class "Default")
      (node (ref "C1") (pin "1") (pinfunction "1_1") (pintype "passive"))
      (node (ref "IC1") (pin "1") (pinfunction "VOUT_1") (pintype "bidirectional"))
      (node (ref "J1") (pin "4") (pinfunction "VDD_4") (pintype "bidirectional"))
    )
    (net (code "85") (name "SD_PWR_ON") (class "Default")
      (node (ref "IC1") (pin "4") (pinfunction "EN/~{EN}_4") (pintype "bidirectional"))
      (node (ref "R1") (pin "2") (pinfunction "2_2") (pintype "passive"))
      (node (ref "RPI-CM2") (pin "75") (pinfunction "SD_PWR_ON_75") (pintype "passive"))
    )
    (net (code "86") (name "unconnected-(IC1-~{FLG}-Pad3)") (class "Default")
      (node (ref "IC1") (pin "3") (pinfunction "~{FLG}_3") (pintype "bidirectional"))
    )
    (net (code "87") (name "unconnected-(IC4-D2+-Pad4)") (class "Default")
      (node (ref "IC4") (pin "4") (pinfunction "D2+_4") (pintype "bidirectional"))
    )
    (net (code "88") (name "unconnected-(IC4-D2--Pad5)") (class "Default")
      (node (ref "IC4") (pin "5") (pinfunction "D2-_5") (pintype "bidirectional"))
    )
    (net (code "89") (name "unconnected-(IC4-N.C._1-Pad6)") (class "Default")
      (node (ref "IC4") (pin "6") (pinfunction "N.C._1_6") (pintype "bidirectional"))
    )
    (net (code "90") (name "unconnected-(IC4-N.C._2-Pad7)") (class "Default")
      (node (ref "IC4") (pin "7") (pinfunction "N.C._2_7") (pintype "bidirectional"))
    )
    (net (code "91") (name "unconnected-(IC4-N.C._3-Pad9)") (class "Default")
      (node (ref "IC4") (pin "9") (pinfunction "N.C._3_9") (pintype "bidirectional"))
    )
    (net (code "92") (name "unconnected-(IC4-N.C._4-Pad10)") (class "Default")
      (node (ref "IC4") (pin "10") (pinfunction "N.C._4_10") (pintype "bidirectional"))
    )
    (net (code "93") (name "unconnected-(J2-Pad1)") (class "Default")
      (node (ref "J2") (pin "1") (pinfunction "1_1") (pintype "passive"))
    )
    (net (code "94") (name "unconnected-(J2-Pad2)") (class "Default")
      (node (ref "J2") (pin "2") (pinfunction "2_2") (pintype "passive"))
    )
    (net (code "95") (name "unconnected-(J2-Pad3)") (class "Default")
      (node (ref "J2") (pin "3") (pinfunction "3_3") (pintype "passive"))
    )
    (net (code "96") (name "unconnected-(J2-Pad4)") (class "Default")
      (node (ref "J2") (pin "4") (pinfunction "4_4") (pintype "passive"))
    )
    (net (code "97") (name "unconnected-(J2-Pad5)") (class "Default")
      (node (ref "J2") (pin "5") (pinfunction "5_5") (pintype "passive"))
    )
    (net (code "98") (name "unconnected-(J2-Pad6)") (class "Default")
      (node (ref "J2") (pin "6") (pinfunction "6_6") (pintype "passive"))
    )
    (net (code "99") (name "unconnected-(J2-Pad7)") (class "Default")
      (node (ref "J2") (pin "7") (pinfunction "7_7") (pintype "passive"))
    )
    (net (code "100") (name "unconnected-(J2-Pad8)") (class "Default")
      (node (ref "J2") (pin "8") (pinfunction "8_8") (pintype "passive"))
    )
    (net (code "101") (name "unconnected-(J3-UTILITY{slash}HEAC+-Pad14)") (class "Default")
      (node (ref "J3") (pin "14") (pinfunction "UTILITY/HEAC+_14") (pintype "passive"))
    )
    (net (code "102") (name "unconnected-(J5-ID-Pad4)") (class "Default")
      (node (ref "J5") (pin "4") (pinfunction "ID_4") (pintype "passive"))
    )
    (net (code "103") (name "unconnected-(RPI-CM2A-ANALOGP0-Pad96)") (class "Default")
      (node (ref "RPI-CM2") (pin "96") (pinfunction "ANALOGP0_96") (pintype "passive"))
    )
    (net (code "104") (name "unconnected-(RPI-CM2A-ANALOGP1-Pad94)") (class "Default")
      (node (ref "RPI-CM2") (pin "94") (pinfunction "ANALOGP1_94") (pintype "passive"))
    )
    (net (code "105") (name "unconnected-(RPI-CM2A-BT_~{DISABLE}-Pad91)") (class "Default")
      (node (ref "RPI-CM2") (pin "91") (pinfunction "BT_~{DISABLE}_91") (pintype "passive"))
    )
    (net (code "106") (name "unconnected-(RPI-CM2A-CAMERA_GPIO-Pad97)") (class "Default")
      (node (ref "RPI-CM2") (pin "97") (pinfunction "CAMERA_GPIO_97") (pintype "passive"))
    )
    (net (code "107") (name "unconnected-(RPI-CM2A-ETH_PAIR0_N-Pad10)") (class "Default")
      (node (ref "RPI-CM2") (pin "10") (pinfunction "ETH_PAIR0_N_10") (pintype "passive"))
    )
    (net (code "108") (name "unconnected-(RPI-CM2A-ETH_PAIR0_P-Pad12)") (class "Default")
      (node (ref "RPI-CM2") (pin "12") (pinfunction "ETH_PAIR0_P_12") (pintype "passive"))
    )
    (net (code "109") (name "unconnected-(RPI-CM2A-ETH_PAIR1_N-Pad6)") (class "Default")
      (node (ref "RPI-CM2") (pin "6") (pinfunction "ETH_PAIR1_N_6") (pintype "passive"))
    )
    (net (code "110") (name "unconnected-(RPI-CM2A-ETH_PAIR1_P-Pad4)") (class "Default")
      (node (ref "RPI-CM2") (pin "4") (pinfunction "ETH_PAIR1_P_4") (pintype "passive"))
    )
    (net (code "111") (name "unconnected-(RPI-CM2A-ETH_PAIR2_N-Pad9)") (class "Default")
      (node (ref "RPI-CM2") (pin "9") (pinfunction "ETH_PAIR2_N_9") (pintype "passive"))
    )
    (net (code "112") (name "unconnected-(RPI-CM2A-ETH_PAIR2_P-Pad11)") (class "Default")
      (node (ref "RPI-CM2") (pin "11") (pinfunction "ETH_PAIR2_P_11") (pintype "passive"))
    )
    (net (code "113") (name "unconnected-(RPI-CM2A-ETH_PAIR3_N-Pad5)") (class "Default")
      (node (ref "RPI-CM2") (pin "5") (pinfunction "ETH_PAIR3_N_5") (pintype "passive"))
    )
    (net (code "114") (name "unconnected-(RPI-CM2A-ETH_PAIR3_P-Pad3)") (class "Default")
      (node (ref "RPI-CM2") (pin "3") (pinfunction "ETH_PAIR3_P_3") (pintype "passive"))
    )
    (net (code "115") (name "unconnected-(RPI-CM2A-ETH_SYNC_IN-Pad16)") (class "Default")
      (node (ref "RPI-CM2") (pin "16") (pinfunction "ETH_SYNC_IN_16") (pintype "passive"))
    )
    (net (code "116") (name "unconnected-(RPI-CM2A-ETH_SYNC_OUT-Pad18)") (class "Default")
      (node (ref "RPI-CM2") (pin "18") (pinfunction "ETH_SYNC_OUT_18") (pintype "passive"))
    )
    (net (code "117") (name "unconnected-(RPI-CM2A-ETH_~{LED1}-Pad19)") (class "Default")
      (node (ref "RPI-CM2") (pin "19") (pinfunction "ETH_~{LED1}_19") (pintype "passive"))
    )
    (net (code "118") (name "unconnected-(RPI-CM2A-RESERVED-Pad76)") (class "Default")
      (node (ref "RPI-CM2") (pin "76") (pinfunction "RESERVED_76") (pintype "passive"))
    )
    (net (code "119") (name "unconnected-(RPI-CM2A-SCL0-Pad80)") (class "Default")
      (node (ref "RPI-CM2") (pin "80") (pinfunction "SCL0_80") (pintype "passive"))
    )
    (net (code "120") (name "unconnected-(RPI-CM2A-SDA0-Pad82)") (class "Default")
      (node (ref "RPI-CM2") (pin "82") (pinfunction "SDA0_82") (pintype "passive"))
    )
    (net (code "121") (name "unconnected-(RPI-CM2A-SD_DAT4-Pad68)") (class "Default")
      (node (ref "RPI-CM2") (pin "68") (pinfunction "SD_DAT4_68") (pintype "passive"))
    )
    (net (code "122") (name "unconnected-(RPI-CM2A-SD_DAT5-Pad64)") (class "Default")
      (node (ref "RPI-CM2") (pin "64") (pinfunction "SD_DAT5_64") (pintype "passive"))
    )
    (net (code "123") (name "unconnected-(RPI-CM2A-SD_DAT6-Pad72)") (class "Default")
      (node (ref "RPI-CM2") (pin "72") (pinfunction "SD_DAT6_72") (pintype "passive"))
    )
    (net (code "124") (name "unconnected-(RPI-CM2A-SD_DAT7-Pad70)") (class "Default")
      (node (ref "RPI-CM2") (pin "70") (pinfunction "SD_DAT7_70") (pintype "passive"))
    )
    (net (code "125") (name "unconnected-(RPI-CM2A-SD_VDD_OVERRIDE-Pad73)") (class "Default")
      (node (ref "RPI-CM2") (pin "73") (pinfunction "SD_VDD_OVERRIDE_73") (pintype "passive"))
    )
    (net (code "126") (name "unconnected-(RPI-CM2A-WL_~{DISABLE}-Pad89)") (class "Default")
      (node (ref "RPI-CM2") (pin "89") (pinfunction "WL_~{DISABLE}_89") (pintype "passive"))
    )
    (net (code "127") (name "unconnected-(RPI-CM2A-~{EXTRST}-Pad100)") (class "Default")
      (node (ref "RPI-CM2") (pin "100") (pinfunction "~{EXTRST}_100") (pintype "passive"))
    )
    (net (code "128") (name "unconnected-(RPI-CM2B-CAM0_C_N-Pad140)") (class "Default")
      (node (ref "RPI-CM2") (pin "140") (pinfunction "CAM0_C_N_140") (pintype "passive"))
    )
    (net (code "129") (name "unconnected-(RPI-CM2B-CAM0_C_P-Pad142)") (class "Default")
      (node (ref "RPI-CM2") (pin "142") (pinfunction "CAM0_C_P_142") (pintype "passive"))
    )
    (net (code "130") (name "unconnected-(RPI-CM2B-CAM0_D0_N-Pad128)") (class "Default")
      (node (ref "RPI-CM2") (pin "128") (pinfunction "CAM0_D0_N_128") (pintype "passive"))
    )
    (net (code "131") (name "unconnected-(RPI-CM2B-CAM0_D0_P-Pad130)") (class "Default")
      (node (ref "RPI-CM2") (pin "130") (pinfunction "CAM0_D0_P_130") (pintype "passive"))
    )
    (net (code "132") (name "unconnected-(RPI-CM2B-CAM0_D1_N-Pad134)") (class "Default")
      (node (ref "RPI-CM2") (pin "134") (pinfunction "CAM0_D1_N_134") (pintype "passive"))
    )
    (net (code "133") (name "unconnected-(RPI-CM2B-CAM0_D1_P-Pad136)") (class "Default")
      (node (ref "RPI-CM2") (pin "136") (pinfunction "CAM0_D1_P_136") (pintype "passive"))
    )
    (net (code "134") (name "unconnected-(RPI-CM2B-CAM1_C_N-Pad127)") (class "Default")
      (node (ref "RPI-CM2") (pin "127") (pinfunction "CAM1_C_N_127") (pintype "passive"))
    )
    (net (code "135") (name "unconnected-(RPI-CM2B-CAM1_C_P-Pad129)") (class "Default")
      (node (ref "RPI-CM2") (pin "129") (pinfunction "CAM1_C_P_129") (pintype "passive"))
    )
    (net (code "136") (name "unconnected-(RPI-CM2B-CAM1_D0_N-Pad115)") (class "Default")
      (node (ref "RPI-CM2") (pin "115") (pinfunction "CAM1_D0_N_115") (pintype "passive"))
    )
    (net (code "137") (name "unconnected-(RPI-CM2B-CAM1_D0_P-Pad117)") (class "Default")
      (node (ref "RPI-CM2") (pin "117") (pinfunction "CAM1_D0_P_117") (pintype "passive"))
    )
    (net (code "138") (name "unconnected-(RPI-CM2B-CAM1_D1_N-Pad121)") (class "Default")
      (node (ref "RPI-CM2") (pin "121") (pinfunction "CAM1_D1_N_121") (pintype "passive"))
    )
    (net (code "139") (name "unconnected-(RPI-CM2B-CAM1_D1_P-Pad123)") (class "Default")
      (node (ref "RPI-CM2") (pin "123") (pinfunction "CAM1_D1_P_123") (pintype "passive"))
    )
    (net (code "140") (name "unconnected-(RPI-CM2B-CAM1_D2_N-Pad133)") (class "Default")
      (node (ref "RPI-CM2") (pin "133") (pinfunction "CAM1_D2_N_133") (pintype "passive"))
    )
    (net (code "141") (name "unconnected-(RPI-CM2B-CAM1_D2_P-Pad135)") (class "Default")
      (node (ref "RPI-CM2") (pin "135") (pinfunction "CAM1_D2_P_135") (pintype "passive"))
    )
    (net (code "142") (name "unconnected-(RPI-CM2B-CAM1_D3_N-Pad139)") (class "Default")
      (node (ref "RPI-CM2") (pin "139") (pinfunction "CAM1_D3_N_139") (pintype "passive"))
    )
    (net (code "143") (name "unconnected-(RPI-CM2B-CAM1_D3_P-Pad141)") (class "Default")
      (node (ref "RPI-CM2") (pin "141") (pinfunction "CAM1_D3_P_141") (pintype "passive"))
    )
    (net (code "144") (name "unconnected-(RPI-CM2B-DSI0_C_N-Pad169)") (class "Default")
      (node (ref "RPI-CM2") (pin "169") (pinfunction "DSI0_C_N_169") (pintype "passive"))
    )
    (net (code "145") (name "unconnected-(RPI-CM2B-DSI0_C_P-Pad171)") (class "Default")
      (node (ref "RPI-CM2") (pin "171") (pinfunction "DSI0_C_P_171") (pintype "passive"))
    )
    (net (code "146") (name "unconnected-(RPI-CM2B-DSI0_D0_N-Pad157)") (class "Default")
      (node (ref "RPI-CM2") (pin "157") (pinfunction "DSI0_D0_N_157") (pintype "passive"))
    )
    (net (code "147") (name "unconnected-(RPI-CM2B-DSI0_D0_P-Pad159)") (class "Default")
      (node (ref "RPI-CM2") (pin "159") (pinfunction "DSI0_D0_P_159") (pintype "passive"))
    )
    (net (code "148") (name "unconnected-(RPI-CM2B-DSI0_D1_N-Pad163)") (class "Default")
      (node (ref "RPI-CM2") (pin "163") (pinfunction "DSI0_D1_N_163") (pintype "passive"))
    )
    (net (code "149") (name "unconnected-(RPI-CM2B-DSI0_D1_P-Pad165)") (class "Default")
      (node (ref "RPI-CM2") (pin "165") (pinfunction "DSI0_D1_P_165") (pintype "passive"))
    )
    (net (code "150") (name "unconnected-(RPI-CM2B-DSI1_C_N-Pad187)") (class "Default")
      (node (ref "RPI-CM2") (pin "187") (pinfunction "DSI1_C_N_187") (pintype "passive"))
    )
    (net (code "151") (name "unconnected-(RPI-CM2B-DSI1_C_P-Pad189)") (class "Default")
      (node (ref "RPI-CM2") (pin "189") (pinfunction "DSI1_C_P_189") (pintype "passive"))
    )
    (net (code "152") (name "unconnected-(RPI-CM2B-DSI1_D0_N-Pad175)") (class "Default")
      (node (ref "RPI-CM2") (pin "175") (pinfunction "DSI1_D0_N_175") (pintype "passive"))
    )
    (net (code "153") (name "unconnected-(RPI-CM2B-DSI1_D0_P-Pad177)") (class "Default")
      (node (ref "RPI-CM2") (pin "177") (pinfunction "DSI1_D0_P_177") (pintype "passive"))
    )
    (net (code "154") (name "unconnected-(RPI-CM2B-DSI1_D1_N-Pad181)") (class "Default")
      (node (ref "RPI-CM2") (pin "181") (pinfunction "DSI1_D1_N_181") (pintype "passive"))
    )
    (net (code "155") (name "unconnected-(RPI-CM2B-DSI1_D1_P-Pad183)") (class "Default")
      (node (ref "RPI-CM2") (pin "183") (pinfunction "DSI1_D1_P_183") (pintype "passive"))
    )
    (net (code "156") (name "unconnected-(RPI-CM2B-DSI1_D2_N-Pad193)") (class "Default")
      (node (ref "RPI-CM2") (pin "193") (pinfunction "DSI1_D2_N_193") (pintype "passive"))
    )
    (net (code "157") (name "unconnected-(RPI-CM2B-DSI1_D2_P-Pad195)") (class "Default")
      (node (ref "RPI-CM2") (pin "195") (pinfunction "DSI1_D2_P_195") (pintype "passive"))
    )
    (net (code "158") (name "unconnected-(RPI-CM2B-DSI1_D3_N-Pad194)") (class "Default")
      (node (ref "RPI-CM2") (pin "194") (pinfunction "DSI1_D3_N_194") (pintype "passive"))
    )
    (net (code "159") (name "unconnected-(RPI-CM2B-DSI1_D3_P-Pad196)") (class "Default")
      (node (ref "RPI-CM2") (pin "196") (pinfunction "DSI1_D3_P_196") (pintype "passive"))
    )
    (net (code "160") (name "unconnected-(RPI-CM2B-HDMI1_CEC-Pad149)") (class "Default")
      (node (ref "RPI-CM2") (pin "149") (pinfunction "HDMI1_CEC_149") (pintype "passive"))
    )
    (net (code "161") (name "unconnected-(RPI-CM2B-HDMI1_CLK_N-Pad166)") (class "Default")
      (node (ref "RPI-CM2") (pin "166") (pinfunction "HDMI1_CLK_N_166") (pintype "passive"))
    )
    (net (code "162") (name "unconnected-(RPI-CM2B-HDMI1_CLK_P-Pad164)") (class "Default")
      (node (ref "RPI-CM2") (pin "164") (pinfunction "HDMI1_CLK_P_164") (pintype "passive"))
    )
    (net (code "163") (name "unconnected-(RPI-CM2B-HDMI1_HOTPLUG-Pad143)") (class "Default")
      (node (ref "RPI-CM2") (pin "143") (pinfunction "HDMI1_HOTPLUG_143") (pintype "passive"))
    )
    (net (code "164") (name "unconnected-(RPI-CM2B-HDMI1_SCL-Pad147)") (class "Default")
      (node (ref "RPI-CM2") (pin "147") (pinfunction "HDMI1_SCL_147") (pintype "passive"))
    )
    (net (code "165") (name "unconnected-(RPI-CM2B-HDMI1_SDA-Pad145)") (class "Default")
      (node (ref "RPI-CM2") (pin "145") (pinfunction "HDMI1_SDA_145") (pintype "passive"))
    )
    (net (code "166") (name "unconnected-(RPI-CM2B-HDMI1_TX0_N-Pad160)") (class "Default")
      (node (ref "RPI-CM2") (pin "160") (pinfunction "HDMI1_TX0_N_160") (pintype "passive"))
    )
    (net (code "167") (name "unconnected-(RPI-CM2B-HDMI1_TX0_P-Pad158)") (class "Default")
      (node (ref "RPI-CM2") (pin "158") (pinfunction "HDMI1_TX0_P_158") (pintype "passive"))
    )
    (net (code "168") (name "unconnected-(RPI-CM2B-HDMI1_TX1_N-Pad154)") (class "Default")
      (node (ref "RPI-CM2") (pin "154") (pinfunction "HDMI1_TX1_N_154") (pintype "passive"))
    )
    (net (code "169") (name "unconnected-(RPI-CM2B-HDMI1_TX1_P-Pad152)") (class "Default")
      (node (ref "RPI-CM2") (pin "152") (pinfunction "HDMI1_TX1_P_152") (pintype "passive"))
    )
    (net (code "170") (name "unconnected-(RPI-CM2B-HDMI1_TX2_N-Pad148)") (class "Default")
      (node (ref "RPI-CM2") (pin "148") (pinfunction "HDMI1_TX2_N_148") (pintype "passive"))
    )
    (net (code "171") (name "unconnected-(RPI-CM2B-HDMI1_TX2_P-Pad146)") (class "Default")
      (node (ref "RPI-CM2") (pin "146") (pinfunction "HDMI1_TX2_P_146") (pintype "passive"))
    )
    (net (code "172") (name "unconnected-(RPI-CM2B-PCIE_CLK_N-Pad112)") (class "Default")
      (node (ref "RPI-CM2") (pin "112") (pinfunction "PCIE_CLK_N_112") (pintype "passive"))
    )
    (net (code "173") (name "unconnected-(RPI-CM2B-PCIE_CLK_P-Pad110)") (class "Default")
      (node (ref "RPI-CM2") (pin "110") (pinfunction "PCIE_CLK_P_110") (pintype "passive"))
    )
    (net (code "174") (name "unconnected-(RPI-CM2B-PCIE_CLK_~{REQ}-Pad102)") (class "Default")
      (node (ref "RPI-CM2") (pin "102") (pinfunction "PCIE_CLK_~{REQ}_102") (pintype "passive"))
    )
    (net (code "175") (name "unconnected-(RPI-CM2B-PCIE_RX_N-Pad118)") (class "Default")
      (node (ref "RPI-CM2") (pin "118") (pinfunction "PCIE_RX_N_118") (pintype "passive"))
    )
    (net (code "176") (name "unconnected-(RPI-CM2B-PCIE_RX_P-Pad116)") (class "Default")
      (node (ref "RPI-CM2") (pin "116") (pinfunction "PCIE_RX_P_116") (pintype "passive"))
    )
    (net (code "177") (name "unconnected-(RPI-CM2B-PCIE_TX_N-Pad124)") (class "Default")
      (node (ref "RPI-CM2") (pin "124") (pinfunction "PCIE_TX_N_124") (pintype "passive"))
    )
    (net (code "178") (name "unconnected-(RPI-CM2B-PCIE_TX_P-Pad122)") (class "Default")
      (node (ref "RPI-CM2") (pin "122") (pinfunction "PCIE_TX_P_122") (pintype "passive"))
    )
    (net (code "179") (name "unconnected-(RPI-CM2B-PCIE_~{RST}-Pad109)") (class "Default")
      (node (ref "RPI-CM2") (pin "109") (pinfunction "PCIE_~{RST}_109") (pintype "passive"))
    )
    (net (code "180") (name "unconnected-(RPI-CM2B-RESERVED-Pad104)") (class "Default")
      (node (ref "RPI-CM2") (pin "104") (pinfunction "RESERVED_104") (pintype "passive"))
    )
    (net (code "181") (name "unconnected-(RPI-CM2B-RESERVED-Pad106)") (class "Default")
      (node (ref "RPI-CM2") (pin "106") (pinfunction "RESERVED_106") (pintype "passive"))
    )
    (net (code "182") (name "unconnected-(RPI-CM2B-VDAC_COMP-Pad111)") (class "Default")
      (node (ref "RPI-CM2") (pin "111") (pinfunction "VDAC_COMP_111") (pintype "passive"))
    )
  )
)
